# MakerFaireGent_2025_00.net
KiCad netlist of a schematic drawn in Altium Designer
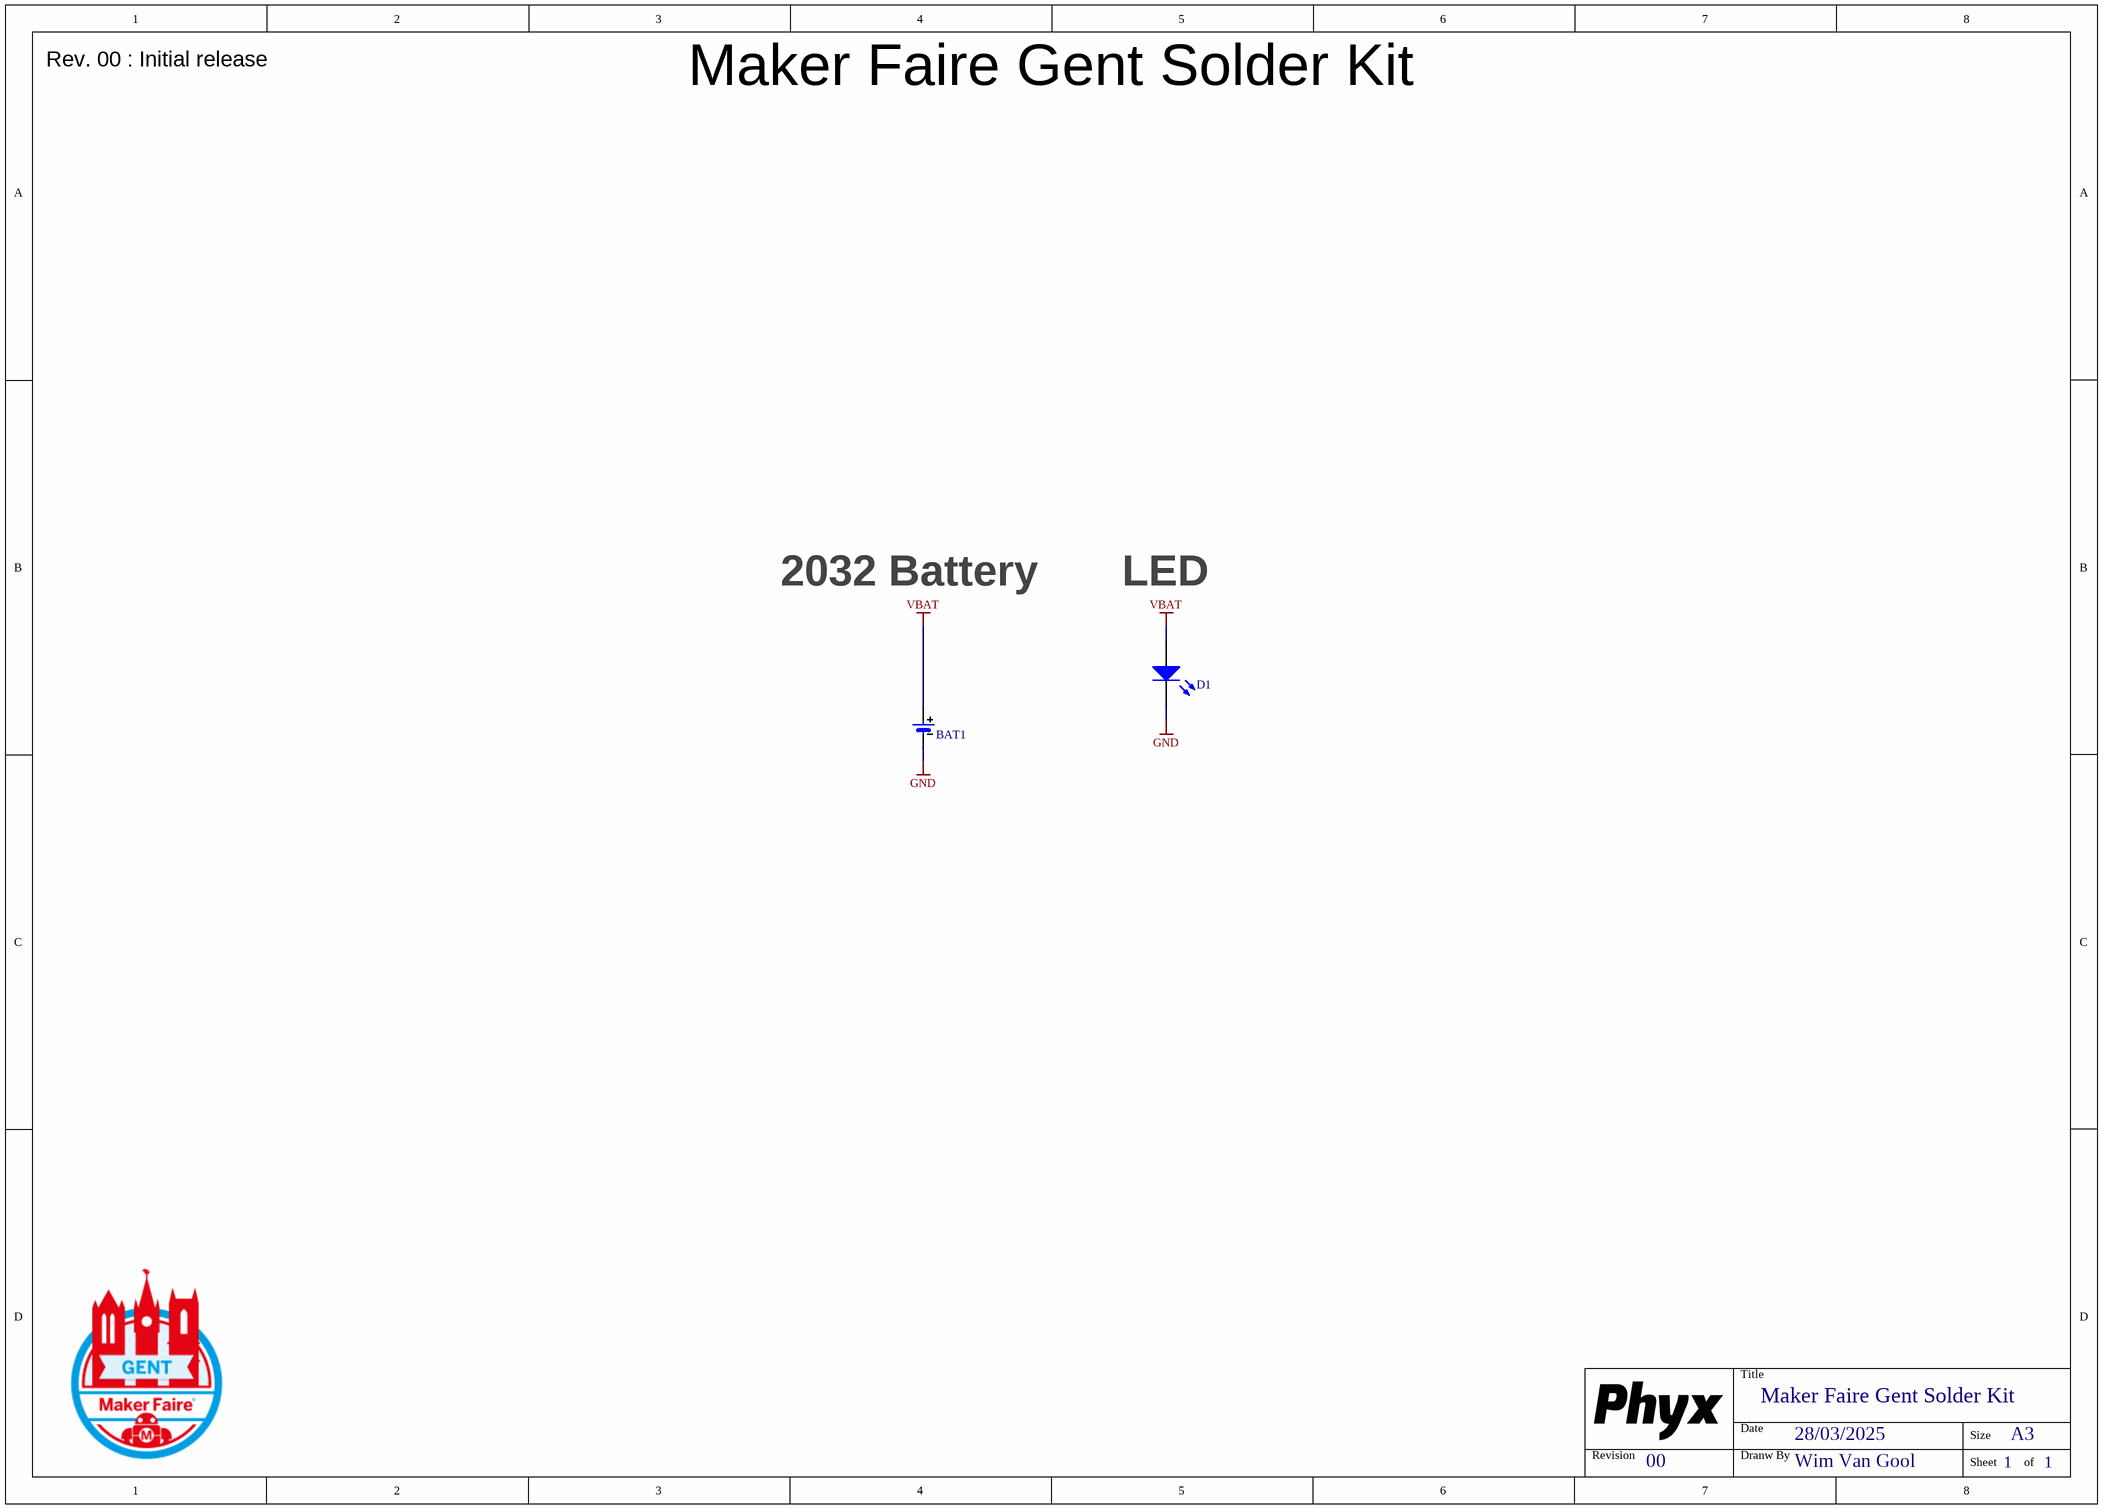
[diagram p0: MakerFaireGent_2025_00.SchDoc]

(export (version "E")
  (design (tool "Eeschema 10.0.6"))
  (components
    (comp (ref "BAT1")
      (value "CR2032 Battery Holder")
      (footprint "BAT_CR2032_China")
      (description "=Description")
      (libsource (lib "Phyx_Components") (part "BAT_2"))
    )
    (comp (ref "D1")
      (value "Default 5mm Blue LED")
      (footprint "LED_5MM_BL")
      (description "LED Blue 5mm")
      (libsource (lib "Phyx_Components") (part "LED_BLUE"))
    )
  )
  (nets
    (net (code "2") (name "GND") (class "Default")
      (node (ref "BAT1") (pin "2") (pinfunction "2_2") (pintype "passive"))
      (node (ref "D1") (pin "2") (pinfunction "K_2") (pintype "passive"))
    )
    (net (code "3") (name "VBAT") (class "Default")
      (node (ref "BAT1") (pin "1") (pinfunction "1_1") (pintype "passive"))
      (node (ref "D1") (pin "1") (pinfunction "A_1") (pintype "passive"))
    )
  )
)
